# PCE128_rev_B.net
KiCad netlist of a schematic drawn in EAGLE
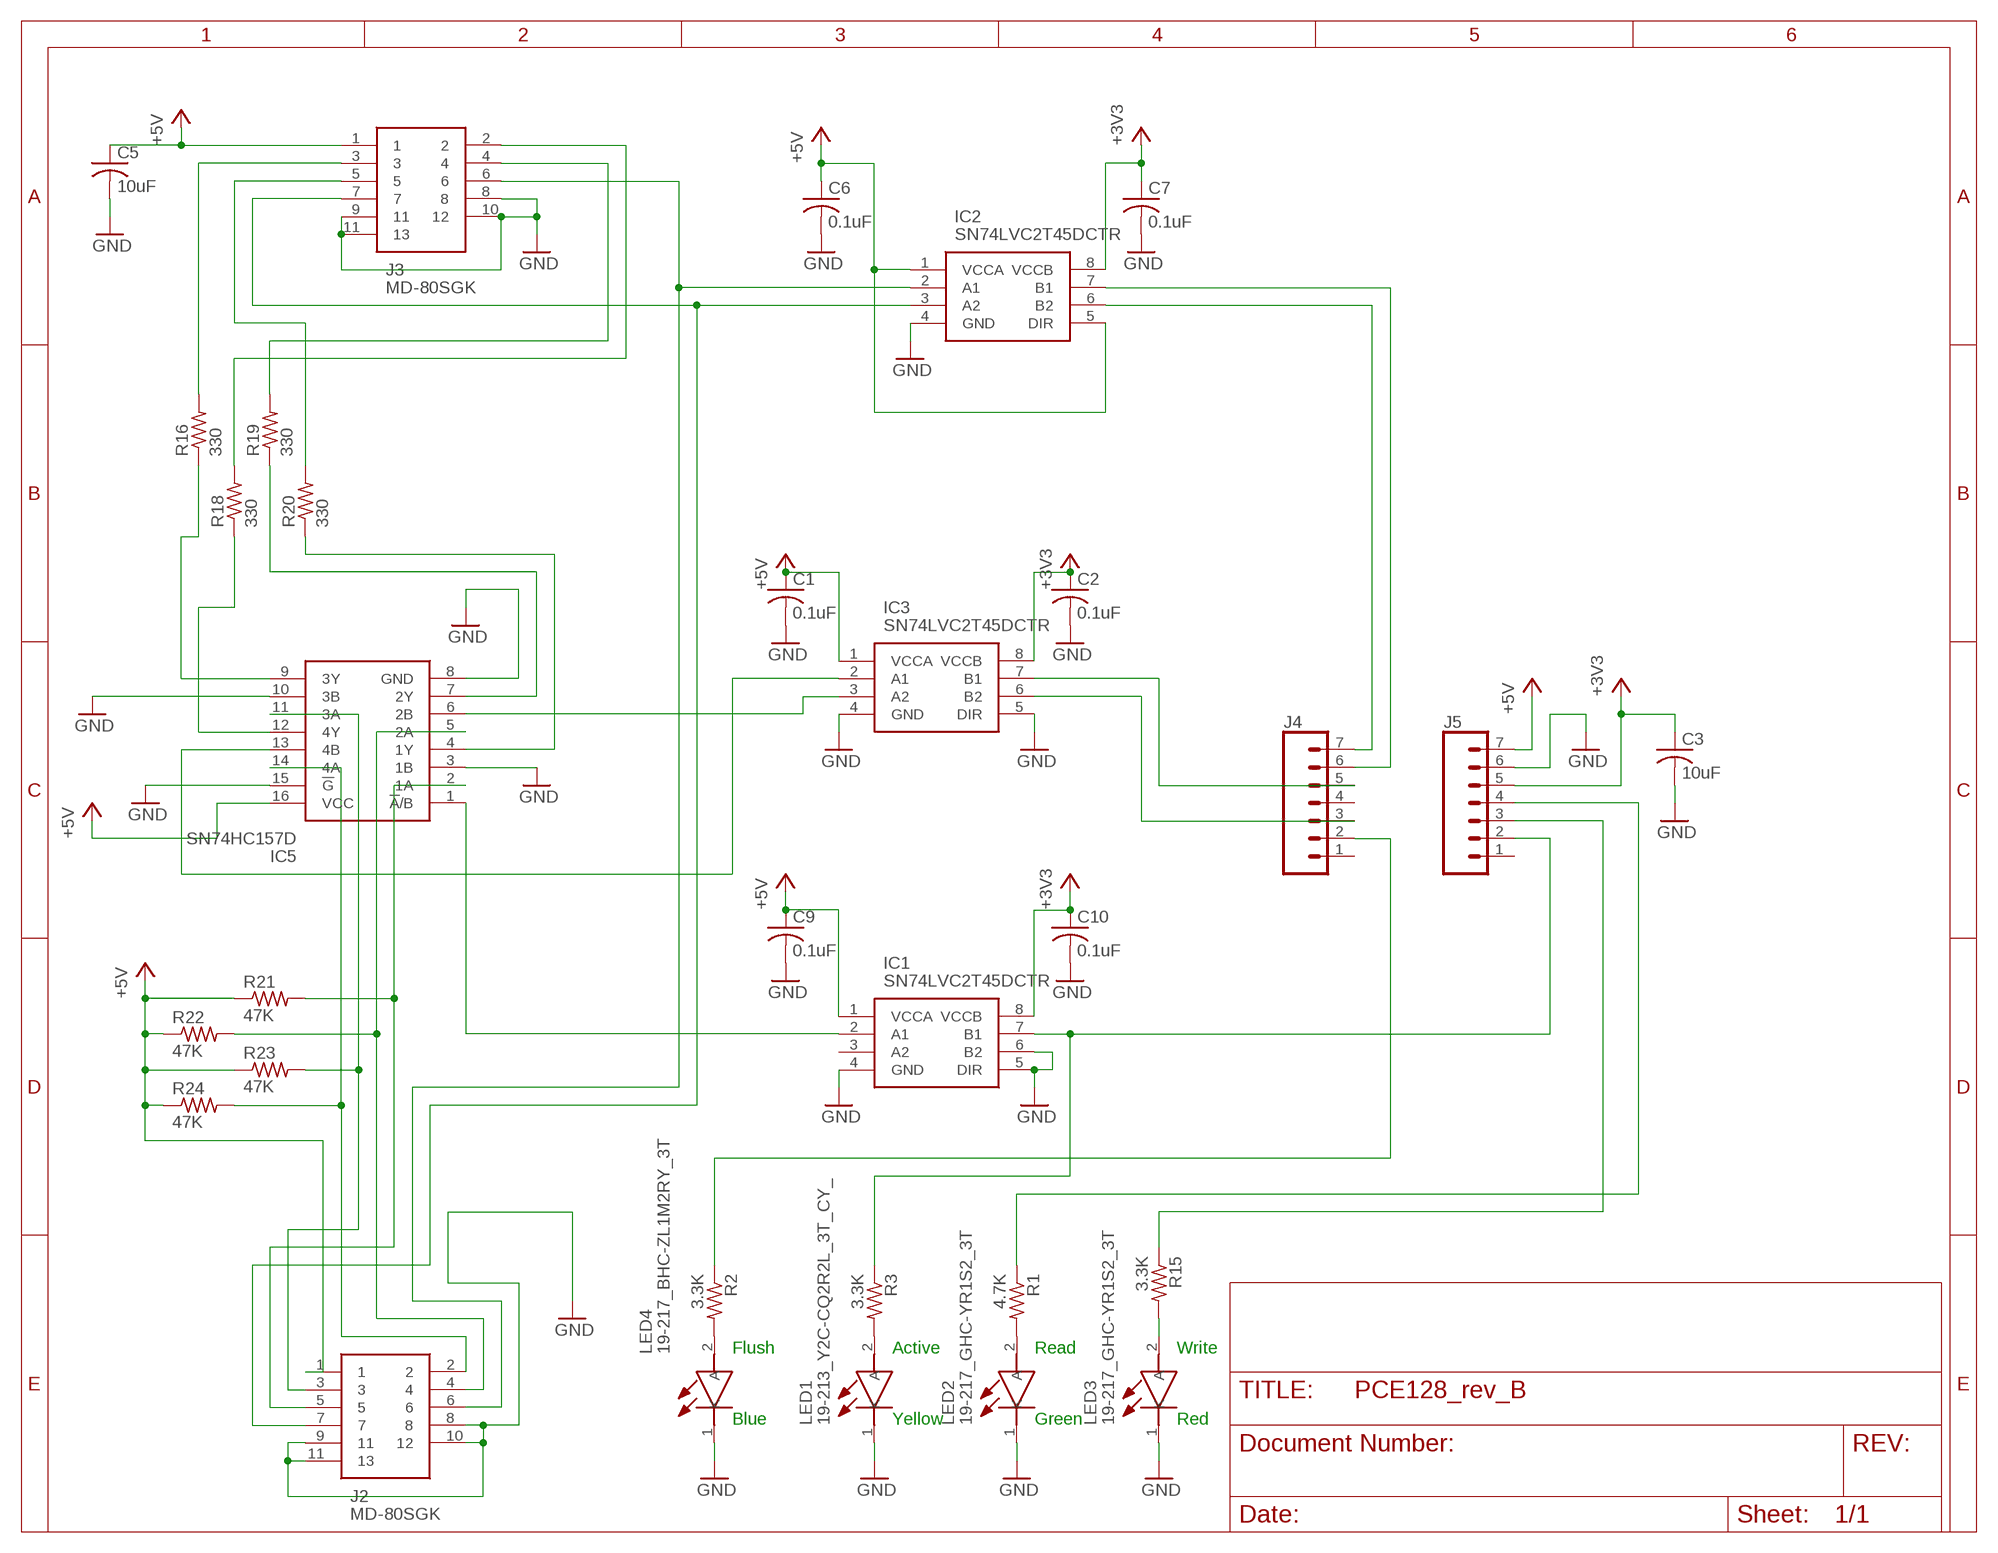
[diagram p0: schematic, sheet 1]

(export (version "E")
  (design (tool "Eeschema 10.0.6"))
  (components
    (comp (ref "C1")
      (value "0.1uF")
      (footprint "eagle-import:C0402")
      (libsource (lib "eagle-import") (part "C-USC0402"))
    )
    (comp (ref "C2")
      (value "0.1uF")
      (footprint "eagle-import:C0402")
      (libsource (lib "eagle-import") (part "C-USC0402"))
    )
    (comp (ref "C3")
      (value "10uF")
      (footprint "eagle-import:C0805")
      (libsource (lib "eagle-import") (part "C-USC0805"))
    )
    (comp (ref "C5")
      (value "10uF")
      (footprint "eagle-import:C0805")
      (libsource (lib "eagle-import") (part "C-USC0805"))
    )
    (comp (ref "C6")
      (value "0.1uF")
      (footprint "eagle-import:C0402")
      (libsource (lib "eagle-import") (part "C-USC0402"))
    )
    (comp (ref "C7")
      (value "0.1uF")
      (footprint "eagle-import:C0402")
      (libsource (lib "eagle-import") (part "C-USC0402"))
    )
    (comp (ref "C9")
      (value "0.1uF")
      (footprint "eagle-import:C0402")
      (libsource (lib "eagle-import") (part "C-USC0402"))
    )
    (comp (ref "C10")
      (value "0.1uF")
      (footprint "eagle-import:C0402")
      (libsource (lib "eagle-import") (part "C-USC0402"))
    )
    (comp (ref "IC1")
      (value "SN74LVC2T45DCTR")
      (footprint "eagle-import:SOP65P400X130-8N")
      (fields
        (field (name "MOUSER_PART_NUMBER") "595-SN74LVC2T45DCTR")
        (field (name "RS_PART_NUMBER") "9213022")
      )
      (libsource (lib "eagle-import") (part "SN74LVC2T45DCTR"))
    )
    (comp (ref "IC2")
      (value "SN74LVC2T45DCTR")
      (footprint "eagle-import:SOP65P400X130-8N")
      (fields
        (field (name "MOUSER_PART_NUMBER") "595-SN74LVC2T45DCTR")
        (field (name "RS_PART_NUMBER") "9213022")
      )
      (libsource (lib "eagle-import") (part "SN74LVC2T45DCTR"))
    )
    (comp (ref "IC3")
      (value "SN74LVC2T45DCTR")
      (footprint "eagle-import:SOP65P400X130-8N")
      (fields
        (field (name "MOUSER_PART_NUMBER") "595-SN74LVC2T45DCTR")
        (field (name "RS_PART_NUMBER") "9213022")
      )
      (libsource (lib "eagle-import") (part "SN74LVC2T45DCTR"))
    )
    (comp (ref "IC5")
      (value "SN74HC157D")
      (footprint "eagle-import:SOIC127P600X175-16N")
      (fields (field (name "MOUSER_PART_NUMBER") "595-SN74HC157D"))
      (libsource (lib "eagle-import") (part "SN74HC157D"))
    )
    (comp (ref "J2")
      (value "MD-80SGK")
      (footprint "eagle-import:MD80SGK")
      (fields (field (name "MOUSER_PART_NUMBER") "490-MD-80SGK"))
      (libsource (lib "eagle-import") (part "MD-80SGK"))
    )
    (comp (ref "J3")
      (value "MD-80SGK")
      (footprint "eagle-import:MD80SGK")
      (fields (field (name "MOUSER_PART_NUMBER") "490-MD-80SGK"))
      (libsource (lib "eagle-import") (part "MD-80SGK"))
    )
    (comp (ref "J4")
      (value "CONN_07NO_SILK")
      (footprint "eagle-import:1X07_NO_SILK")
      (libsource (lib "eagle-import") (part "CONN_07NO_SILK"))
    )
    (comp (ref "J5")
      (value "CONN_07NO_SILK")
      (footprint "eagle-import:1X07_NO_SILK")
      (libsource (lib "eagle-import") (part "CONN_07NO_SILK"))
    )
    (comp (ref "LED1")
      (value "19-213_Y2C-CQ2R2L_3T_CY_")
      (footprint "eagle-import:LEDC1608X50N")
      (fields (field (name "ARROW_PART_NUMBER") "19-213/Y2C-CQ2R2L/3T(CY)"))
      (libsource (lib "eagle-import") (part "19-213_Y2C-CQ2R2L_3T_CY_"))
    )
    (comp (ref "LED2")
      (value "19-217_GHC-YR1S2_3T")
      (footprint "eagle-import:LEDC1608X50N")
      (fields
        (field (name "ARROW_PART_NUMBER") "19-217/GHC-YR1S2/3T")
        (field (name "MOUSER_PART_NUMBER") "638-19217GHCYR1S23T")
      )
      (libsource (lib "eagle-import") (part "19-217_GHC-YR1S2_3T"))
    )
    (comp (ref "LED3")
      (value "19-217_GHC-YR1S2_3T")
      (footprint "eagle-import:LEDC1608X50N")
      (fields
        (field (name "ARROW_PART_NUMBER") "19-217/GHC-YR1S2/3T")
        (field (name "MOUSER_PART_NUMBER") "638-19217GHCYR1S23T")
        (field (name "MANUFACTURER_NAME") "Hubei Kento")
        (field (name "MANUFACTURER_PART_NUMBER") "KT-0603R")
      )
      (libsource (lib "eagle-import") (part "19-217_GHC-YR1S2_3T"))
    )
    (comp (ref "LED4")
      (value "19-217_BHC-ZL1M2RY_3T")
      (footprint "eagle-import:LEDC1608X50N")
      (libsource (lib "eagle-import") (part "19-217_BHC-ZL1M2RY_3T"))
    )
    (comp (ref "R1")
      (value "4.7K")
      (footprint "eagle-import:R0402")
      (libsource (lib "eagle-import") (part "R-US_R0402"))
    )
    (comp (ref "R2")
      (value "3.3K")
      (footprint "eagle-import:R0402")
      (libsource (lib "eagle-import") (part "R-US_R0402"))
    )
    (comp (ref "R3")
      (value "3.3K")
      (footprint "eagle-import:R0402")
      (libsource (lib "eagle-import") (part "R-US_R0402"))
    )
    (comp (ref "R15")
      (value "3.3K")
      (footprint "eagle-import:R0402")
      (libsource (lib "eagle-import") (part "R-US_R0402"))
    )
    (comp (ref "R16")
      (value "330")
      (footprint "eagle-import:R0402")
      (libsource (lib "eagle-import") (part "R-US_R0402"))
    )
    (comp (ref "R18")
      (value "330")
      (footprint "eagle-import:R0402")
      (libsource (lib "eagle-import") (part "R-US_R0402"))
    )
    (comp (ref "R19")
      (value "330")
      (footprint "eagle-import:R0402")
      (libsource (lib "eagle-import") (part "R-US_R0402"))
    )
    (comp (ref "R20")
      (value "330")
      (footprint "eagle-import:R0402")
      (libsource (lib "eagle-import") (part "R-US_R0402"))
    )
    (comp (ref "R21")
      (value "47K")
      (footprint "eagle-import:R0402")
      (libsource (lib "eagle-import") (part "R-US_R0402"))
    )
    (comp (ref "R22")
      (value "47K")
      (footprint "eagle-import:R0402")
      (libsource (lib "eagle-import") (part "R-US_R0402"))
    )
    (comp (ref "R23")
      (value "47K")
      (footprint "eagle-import:R0402")
      (libsource (lib "eagle-import") (part "R-US_R0402"))
    )
    (comp (ref "R24")
      (value "47K")
      (footprint "eagle-import:R0402")
      (libsource (lib "eagle-import") (part "R-US_R0402"))
    )
  )
  (nets
    (net (code "1") (name "+3V3") (class "Default")
      (node (ref "C10") (pin "1") (pinfunction "1_1") (pintype "passive"))
      (node (ref "C2") (pin "1") (pinfunction "1_1") (pintype "passive"))
      (node (ref "C3") (pin "1") (pinfunction "1_1") (pintype "passive"))
      (node (ref "C7") (pin "1") (pinfunction "1_1") (pintype "passive"))
      (node (ref "IC1") (pin "8") (pinfunction "VCCB_8") (pintype "power_in"))
      (node (ref "IC2") (pin "8") (pinfunction "VCCB_8") (pintype "power_in"))
      (node (ref "IC3") (pin "8") (pinfunction "VCCB_8") (pintype "power_in"))
      (node (ref "J5") (pin "5") (pinfunction "5_5") (pintype "passive"))
    )
    (net (code "2") (name "+5V") (class "Default")
      (node (ref "C1") (pin "1") (pinfunction "1_1") (pintype "passive"))
      (node (ref "C5") (pin "1") (pinfunction "1_1") (pintype "passive"))
      (node (ref "C6") (pin "1") (pinfunction "1_1") (pintype "passive"))
      (node (ref "C9") (pin "1") (pinfunction "1_1") (pintype "passive"))
      (node (ref "IC1") (pin "1") (pinfunction "VCCA_1") (pintype "power_in"))
      (node (ref "IC2") (pin "1") (pinfunction "VCCA_1") (pintype "power_in"))
      (node (ref "IC2") (pin "5") (pinfunction "DIR_5") (pintype "bidirectional"))
      (node (ref "IC3") (pin "1") (pinfunction "VCCA_1") (pintype "power_in"))
      (node (ref "IC5") (pin "16") (pinfunction "VCC_16") (pintype "bidirectional"))
      (node (ref "J2") (pin "1") (pinfunction "1_1") (pintype "bidirectional"))
      (node (ref "J3") (pin "1") (pinfunction "1_1") (pintype "bidirectional"))
      (node (ref "J5") (pin "7") (pinfunction "7_7") (pintype "passive"))
      (node (ref "R21") (pin "1") (pinfunction "1_1") (pintype "passive"))
      (node (ref "R22") (pin "1") (pinfunction "1_1") (pintype "passive"))
      (node (ref "R23") (pin "1") (pinfunction "1_1") (pintype "passive"))
      (node (ref "R24") (pin "1") (pinfunction "1_1") (pintype "passive"))
    )
    (net (code "3") (name "GND") (class "Default")
      (node (ref "C1") (pin "2") (pinfunction "2_2") (pintype "passive"))
      (node (ref "C10") (pin "2") (pinfunction "2_2") (pintype "passive"))
      (node (ref "C2") (pin "2") (pinfunction "2_2") (pintype "passive"))
      (node (ref "C3") (pin "2") (pinfunction "2_2") (pintype "passive"))
      (node (ref "C5") (pin "2") (pinfunction "2_2") (pintype "passive"))
      (node (ref "C6") (pin "2") (pinfunction "2_2") (pintype "passive"))
      (node (ref "C7") (pin "2") (pinfunction "2_2") (pintype "passive"))
      (node (ref "C9") (pin "2") (pinfunction "2_2") (pintype "passive"))
      (node (ref "IC1") (pin "4") (pinfunction "GND_4") (pintype "power_in"))
      (node (ref "IC1") (pin "5") (pinfunction "DIR_5") (pintype "bidirectional"))
      (node (ref "IC1") (pin "6") (pinfunction "B2_6") (pintype "bidirectional"))
      (node (ref "IC2") (pin "4") (pinfunction "GND_4") (pintype "power_in"))
      (node (ref "IC3") (pin "4") (pinfunction "GND_4") (pintype "power_in"))
      (node (ref "IC3") (pin "5") (pinfunction "DIR_5") (pintype "bidirectional"))
      (node (ref "IC5") (pin "10") (pinfunction "3B_10") (pintype "bidirectional"))
      (node (ref "IC5") (pin "15") (pinfunction "~{G}_15") (pintype "bidirectional"))
      (node (ref "IC5") (pin "3") (pinfunction "1B_3") (pintype "bidirectional"))
      (node (ref "IC5") (pin "8") (pinfunction "GND_8") (pintype "bidirectional"))
      (node (ref "J2") (pin "10") (pinfunction "12_10") (pintype "bidirectional"))
      (node (ref "J2") (pin "11") (pinfunction "13_11") (pintype "bidirectional"))
      (node (ref "J2") (pin "8") (pinfunction "8_8") (pintype "bidirectional"))
      (node (ref "J2") (pin "9") (pinfunction "11_9") (pintype "bidirectional"))
      (node (ref "J3") (pin "10") (pinfunction "12_10") (pintype "bidirectional"))
      (node (ref "J3") (pin "11") (pinfunction "13_11") (pintype "bidirectional"))
      (node (ref "J3") (pin "8") (pinfunction "8_8") (pintype "bidirectional"))
      (node (ref "J3") (pin "9") (pinfunction "11_9") (pintype "bidirectional"))
      (node (ref "J5") (pin "6") (pinfunction "6_6") (pintype "passive"))
      (node (ref "LED1") (pin "1") (pinfunction "K_1") (pintype "bidirectional"))
      (node (ref "LED2") (pin "1") (pinfunction "K_1") (pintype "bidirectional"))
      (node (ref "LED3") (pin "1") (pinfunction "K_1") (pintype "bidirectional"))
      (node (ref "LED4") (pin "1") (pinfunction "K_1") (pintype "bidirectional"))
    )
    (net (code "4") (name "Net-(IC1-A1)") (class "Default")
      (node (ref "IC1") (pin "2") (pinfunction "A1_2") (pintype "bidirectional"))
      (node (ref "IC5") (pin "1") (pinfunction "~{A}/B_1") (pintype "bidirectional"))
    )
    (net (code "5") (name "Net-(IC1-B1)") (class "Default")
      (node (ref "IC1") (pin "7") (pinfunction "B1_7") (pintype "bidirectional"))
      (node (ref "J5") (pin "2") (pinfunction "2_2") (pintype "passive"))
      (node (ref "R3") (pin "1") (pinfunction "1_1") (pintype "passive"))
    )
    (net (code "6") (name "Net-(IC2-A1)") (class "Default")
      (node (ref "IC2") (pin "2") (pinfunction "A1_2") (pintype "bidirectional"))
      (node (ref "J2") (pin "6") (pinfunction "6_6") (pintype "bidirectional"))
      (node (ref "J3") (pin "6") (pinfunction "6_6") (pintype "bidirectional"))
    )
    (net (code "7") (name "Net-(IC2-A2)") (class "Default")
      (node (ref "IC2") (pin "3") (pinfunction "A2_3") (pintype "bidirectional"))
      (node (ref "J2") (pin "7") (pinfunction "7_7") (pintype "bidirectional"))
      (node (ref "J3") (pin "7") (pinfunction "7_7") (pintype "bidirectional"))
    )
    (net (code "8") (name "Net-(IC2-B1)") (class "Default")
      (node (ref "IC2") (pin "7") (pinfunction "B1_7") (pintype "bidirectional"))
      (node (ref "J4") (pin "6") (pinfunction "6_6") (pintype "passive"))
    )
    (net (code "9") (name "Net-(IC2-B2)") (class "Default")
      (node (ref "IC2") (pin "6") (pinfunction "B2_6") (pintype "bidirectional"))
      (node (ref "J4") (pin "7") (pinfunction "7_7") (pintype "passive"))
    )
    (net (code "10") (name "Net-(IC3-A1)") (class "Default")
      (node (ref "IC3") (pin "2") (pinfunction "A1_2") (pintype "bidirectional"))
      (node (ref "IC5") (pin "13") (pinfunction "4B_13") (pintype "bidirectional"))
    )
    (net (code "11") (name "Net-(IC3-A2)") (class "Default")
      (node (ref "IC3") (pin "3") (pinfunction "A2_3") (pintype "bidirectional"))
      (node (ref "IC5") (pin "6") (pinfunction "2B_6") (pintype "bidirectional"))
    )
    (net (code "12") (name "Net-(IC3-B1)") (class "Default")
      (node (ref "IC3") (pin "7") (pinfunction "B1_7") (pintype "bidirectional"))
      (node (ref "J4") (pin "5") (pinfunction "5_5") (pintype "passive"))
    )
    (net (code "13") (name "Net-(IC3-B2)") (class "Default")
      (node (ref "IC3") (pin "6") (pinfunction "B2_6") (pintype "bidirectional"))
      (node (ref "J4") (pin "3") (pinfunction "3_3") (pintype "passive"))
    )
    (net (code "14") (name "Net-(IC5-1A)") (class "Default")
      (node (ref "IC5") (pin "2") (pinfunction "1A_2") (pintype "bidirectional"))
      (node (ref "J2") (pin "5") (pinfunction "5_5") (pintype "bidirectional"))
      (node (ref "R21") (pin "2") (pinfunction "2_2") (pintype "passive"))
    )
    (net (code "15") (name "Net-(IC5-1Y)") (class "Default")
      (node (ref "IC5") (pin "4") (pinfunction "1Y_4") (pintype "bidirectional"))
      (node (ref "R20") (pin "1") (pinfunction "1_1") (pintype "passive"))
    )
    (net (code "16") (name "Net-(IC5-2A)") (class "Default")
      (node (ref "IC5") (pin "5") (pinfunction "2A_5") (pintype "bidirectional"))
      (node (ref "J2") (pin "4") (pinfunction "4_4") (pintype "bidirectional"))
      (node (ref "R22") (pin "2") (pinfunction "2_2") (pintype "passive"))
    )
    (net (code "17") (name "Net-(IC5-2Y)") (class "Default")
      (node (ref "IC5") (pin "7") (pinfunction "2Y_7") (pintype "bidirectional"))
      (node (ref "R19") (pin "1") (pinfunction "1_1") (pintype "passive"))
    )
    (net (code "18") (name "Net-(IC5-3A)") (class "Default")
      (node (ref "IC5") (pin "11") (pinfunction "3A_11") (pintype "bidirectional"))
      (node (ref "J2") (pin "3") (pinfunction "3_3") (pintype "bidirectional"))
      (node (ref "R23") (pin "2") (pinfunction "2_2") (pintype "passive"))
    )
    (net (code "19") (name "Net-(IC5-3Y)") (class "Default")
      (node (ref "IC5") (pin "9") (pinfunction "3Y_9") (pintype "bidirectional"))
      (node (ref "R16") (pin "1") (pinfunction "1_1") (pintype "passive"))
    )
    (net (code "20") (name "Net-(IC5-4A)") (class "Default")
      (node (ref "IC5") (pin "14") (pinfunction "4A_14") (pintype "bidirectional"))
      (node (ref "J2") (pin "2") (pinfunction "2_2") (pintype "bidirectional"))
      (node (ref "R24") (pin "2") (pinfunction "2_2") (pintype "passive"))
    )
    (net (code "21") (name "Net-(IC5-4Y)") (class "Default")
      (node (ref "IC5") (pin "12") (pinfunction "4Y_12") (pintype "bidirectional"))
      (node (ref "R18") (pin "1") (pinfunction "1_1") (pintype "passive"))
    )
    (net (code "22") (name "Net-(J3-Pad2)") (class "Default")
      (node (ref "J3") (pin "2") (pinfunction "2_2") (pintype "bidirectional"))
      (node (ref "R18") (pin "2") (pinfunction "2_2") (pintype "passive"))
    )
    (net (code "23") (name "Net-(J3-Pad3)") (class "Default")
      (node (ref "J3") (pin "3") (pinfunction "3_3") (pintype "bidirectional"))
      (node (ref "R16") (pin "2") (pinfunction "2_2") (pintype "passive"))
    )
    (net (code "24") (name "Net-(J3-Pad4)") (class "Default")
      (node (ref "J3") (pin "4") (pinfunction "4_4") (pintype "bidirectional"))
      (node (ref "R19") (pin "2") (pinfunction "2_2") (pintype "passive"))
    )
    (net (code "25") (name "Net-(J3-Pad5)") (class "Default")
      (node (ref "J3") (pin "5") (pinfunction "5_5") (pintype "bidirectional"))
      (node (ref "R20") (pin "2") (pinfunction "2_2") (pintype "passive"))
    )
    (net (code "26") (name "Net-(J4-Pad2)") (class "Default")
      (node (ref "J4") (pin "2") (pinfunction "2_2") (pintype "passive"))
      (node (ref "R2") (pin "1") (pinfunction "1_1") (pintype "passive"))
    )
    (net (code "27") (name "Net-(J5-Pad3)") (class "Default")
      (node (ref "J5") (pin "3") (pinfunction "3_3") (pintype "passive"))
      (node (ref "R15") (pin "1") (pinfunction "1_1") (pintype "passive"))
    )
    (net (code "28") (name "Net-(J5-Pad4)") (class "Default")
      (node (ref "J5") (pin "4") (pinfunction "4_4") (pintype "passive"))
      (node (ref "R1") (pin "1") (pinfunction "1_1") (pintype "passive"))
    )
    (net (code "29") (name "Net-(LED1-A)") (class "Default")
      (node (ref "LED1") (pin "2") (pinfunction "A_2") (pintype "bidirectional"))
      (node (ref "R3") (pin "2") (pinfunction "2_2") (pintype "passive"))
    )
    (net (code "30") (name "Net-(LED2-A)") (class "Default")
      (node (ref "LED2") (pin "2") (pinfunction "A_2") (pintype "bidirectional"))
      (node (ref "R1") (pin "2") (pinfunction "2_2") (pintype "passive"))
    )
    (net (code "31") (name "Net-(LED3-A)") (class "Default")
      (node (ref "LED3") (pin "2") (pinfunction "A_2") (pintype "bidirectional"))
      (node (ref "R15") (pin "2") (pinfunction "2_2") (pintype "passive"))
    )
    (net (code "32") (name "Net-(LED4-A)") (class "Default")
      (node (ref "LED4") (pin "2") (pinfunction "A_2") (pintype "bidirectional"))
      (node (ref "R2") (pin "2") (pinfunction "2_2") (pintype "passive"))
    )
    (net (code "33") (name "unconnected-(IC1-A2-Pad3)") (class "Default")
      (node (ref "IC1") (pin "3") (pinfunction "A2_3") (pintype "bidirectional"))
    )
    (net (code "34") (name "unconnected-(J4-Pad1)") (class "Default")
      (node (ref "J4") (pin "1") (pinfunction "1_1") (pintype "passive"))
    )
    (net (code "35") (name "unconnected-(J4-Pad4)") (class "Default")
      (node (ref "J4") (pin "4") (pinfunction "4_4") (pintype "passive"))
    )
    (net (code "36") (name "unconnected-(J5-Pad1)") (class "Default")
      (node (ref "J5") (pin "1") (pinfunction "1_1") (pintype "passive"))
    )
  )
)
